# sensor_board_v0_1.net
KiCad netlist of a schematic drawn in EAGLE
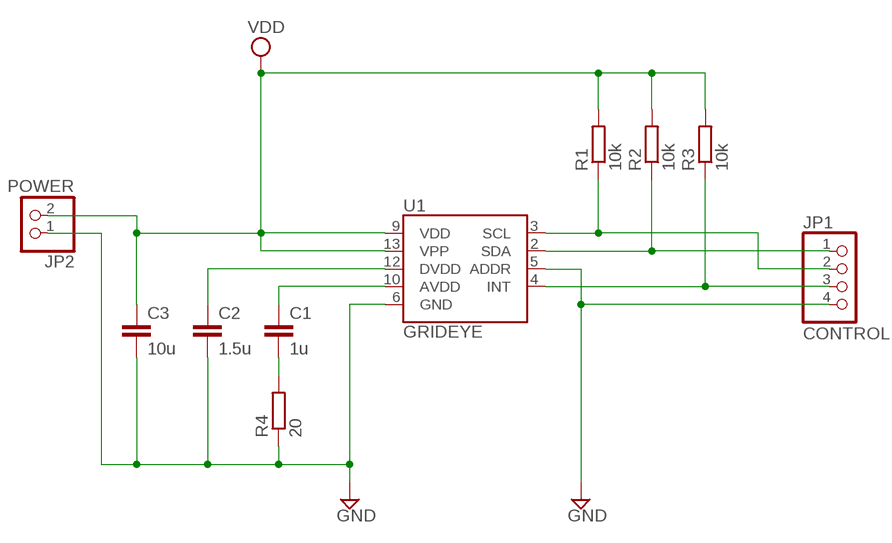
[diagram p0: schematic, sheet 1]

(export (version "E")
  (design (tool "Eeschema 10.0.6"))
  (components
    (comp (ref "C1")
      (value "1u")
      (footprint "eagle-import:C0805")
      (libsource (lib "eagle-import") (part "C-EUC0805"))
    )
    (comp (ref "C2")
      (value "1.5u")
      (footprint "eagle-import:C0805")
      (libsource (lib "eagle-import") (part "C-EUC0805"))
    )
    (comp (ref "C3")
      (value "10u")
      (footprint "eagle-import:C0805")
      (libsource (lib "eagle-import") (part "C-EUC0805"))
    )
    (comp (ref "JP1")
      (value "CONTROL")
      (footprint "eagle-import:1X04")
      (libsource (lib "eagle-import") (part "PINHD-1X4"))
    )
    (comp (ref "JP2")
      (value "POWER")
      (footprint "eagle-import:1X02")
      (libsource (lib "eagle-import") (part "PINHD-1X2"))
    )
    (comp (ref "R1")
      (value "10k")
      (footprint "eagle-import:R0805")
      (libsource (lib "eagle-import") (part "R-EU_R0805"))
    )
    (comp (ref "R2")
      (value "10k")
      (footprint "eagle-import:R0805")
      (libsource (lib "eagle-import") (part "R-EU_R0805"))
    )
    (comp (ref "R3")
      (value "10k")
      (footprint "eagle-import:R0805")
      (libsource (lib "eagle-import") (part "R-EU_R0805"))
    )
    (comp (ref "R4")
      (value "20")
      (footprint "eagle-import:R0805")
      (libsource (lib "eagle-import") (part "R-EU_R0805"))
    )
    (comp (ref "U1")
      (value "GRIDEYE")
      (footprint "eagle-import:GRIDEYE-AMG88")
      (libsource (lib "eagle-import") (part "GRIDEYE"))
    )
  )
  (nets
    (net (code "1") (name "GND") (class "Default")
      (node (ref "C2") (pin "2") (pinfunction "2_2") (pintype "passive"))
      (node (ref "C3") (pin "2") (pinfunction "2_2") (pintype "passive"))
      (node (ref "JP1") (pin "4") (pinfunction "4_4") (pintype "passive"))
      (node (ref "JP2") (pin "1") (pinfunction "1_1") (pintype "passive"))
      (node (ref "R4") (pin "1") (pinfunction "1_1") (pintype "passive"))
      (node (ref "U1") (pin "5") (pinfunction "ADDR_5") (pintype "bidirectional"))
      (node (ref "U1") (pin "6") (pinfunction "GND_6") (pintype "bidirectional"))
    )
    (net (code "2") (name "Net-(C1-Pad2)") (class "Default")
      (node (ref "C1") (pin "2") (pinfunction "2_2") (pintype "passive"))
      (node (ref "R4") (pin "2") (pinfunction "2_2") (pintype "passive"))
    )
    (net (code "3") (name "Net-(U1-AVDD)") (class "Default")
      (node (ref "C1") (pin "1") (pinfunction "1_1") (pintype "passive"))
      (node (ref "U1") (pin "10") (pinfunction "AVDD_10") (pintype "bidirectional"))
    )
    (net (code "4") (name "Net-(U1-DVDD)") (class "Default")
      (node (ref "C2") (pin "1") (pinfunction "1_1") (pintype "passive"))
      (node (ref "U1") (pin "12") (pinfunction "DVDD_12") (pintype "bidirectional"))
    )
    (net (code "5") (name "Net-(U1-INT)") (class "Default")
      (node (ref "JP1") (pin "3") (pinfunction "3_3") (pintype "passive"))
      (node (ref "R3") (pin "1") (pinfunction "1_1") (pintype "passive"))
      (node (ref "U1") (pin "4") (pinfunction "INT_4") (pintype "bidirectional"))
    )
    (net (code "6") (name "Net-(U1-SCL)") (class "Default")
      (node (ref "JP1") (pin "2") (pinfunction "2_2") (pintype "passive"))
      (node (ref "R1") (pin "1") (pinfunction "1_1") (pintype "passive"))
      (node (ref "U1") (pin "3") (pinfunction "SCL_3") (pintype "bidirectional"))
    )
    (net (code "7") (name "Net-(U1-SDA)") (class "Default")
      (node (ref "JP1") (pin "1") (pinfunction "1_1") (pintype "passive"))
      (node (ref "R2") (pin "1") (pinfunction "1_1") (pintype "passive"))
      (node (ref "U1") (pin "2") (pinfunction "SDA_2") (pintype "bidirectional"))
    )
    (net (code "8") (name "VDD") (class "Default")
      (node (ref "C3") (pin "1") (pinfunction "1_1") (pintype "passive"))
      (node (ref "JP2") (pin "2") (pinfunction "2_2") (pintype "passive"))
      (node (ref "R1") (pin "2") (pinfunction "2_2") (pintype "passive"))
      (node (ref "R2") (pin "2") (pinfunction "2_2") (pintype "passive"))
      (node (ref "R3") (pin "2") (pinfunction "2_2") (pintype "passive"))
      (node (ref "U1") (pin "13") (pinfunction "VPP_13") (pintype "bidirectional"))
      (node (ref "U1") (pin "9") (pinfunction "VDD_9") (pintype "bidirectional"))
    )
  )
)
